# CristmasVillage_Driver_1-2.net
KiCad netlist of a schematic drawn in EAGLE
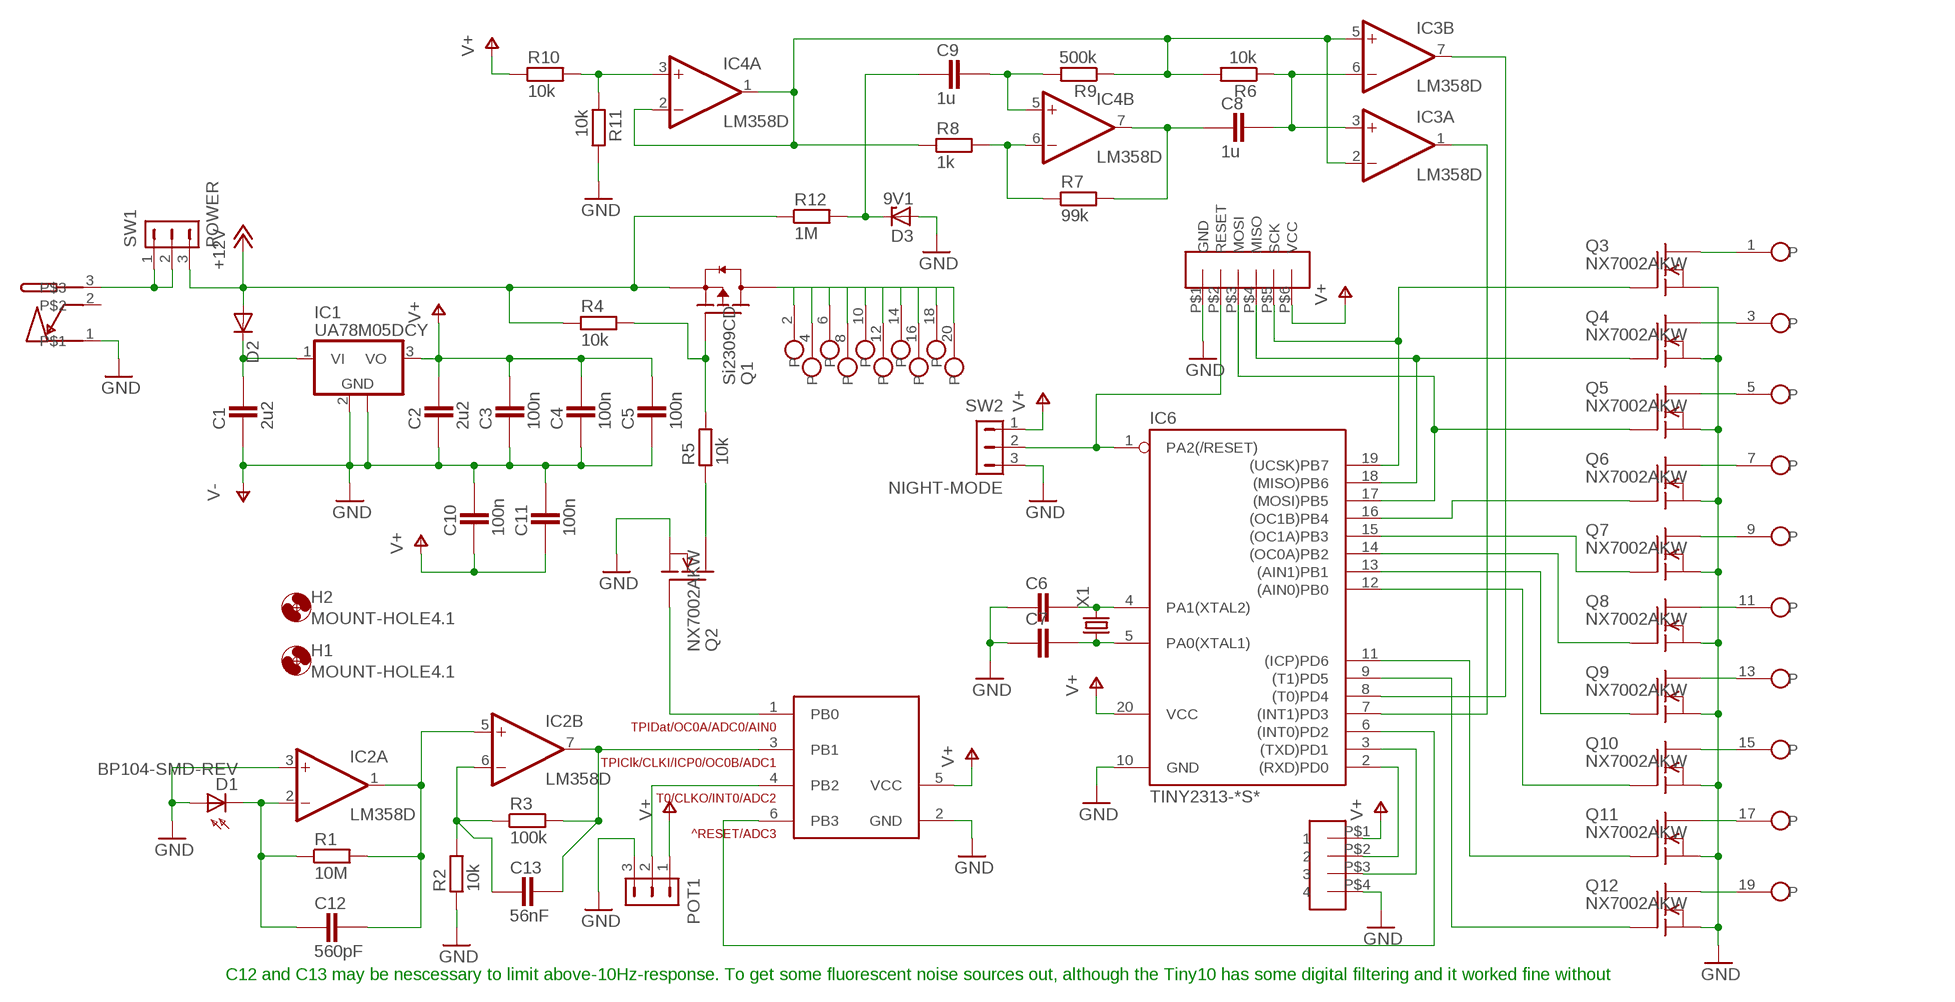
[diagram p0: schematic, sheet 1]

(export (version "E")
  (design (tool "Eeschema 10.0.6"))
  (components
    (comp (ref "C1")
      (value "2u2")
      (footprint "eagle-import:CAPC3215X168N")
      (libsource (lib "eagle-import") (part "CAPACITOR_1206"))
    )
    (comp (ref "C2")
      (value "2u2")
      (footprint "eagle-import:CAPC3215X168N")
      (libsource (lib "eagle-import") (part "CAPACITOR_1206"))
    )
    (comp (ref "C3")
      (value "100n")
      (footprint "eagle-import:CAPC1608X92N")
      (libsource (lib "eagle-import") (part "CAPACITOR_0603"))
    )
    (comp (ref "C4")
      (value "100n")
      (footprint "eagle-import:CAPC1608X92N")
      (libsource (lib "eagle-import") (part "CAPACITOR_0603"))
    )
    (comp (ref "C5")
      (value "100n")
      (footprint "eagle-import:CAPC1608X92N")
      (libsource (lib "eagle-import") (part "CAPACITOR_0603"))
    )
    (comp (ref "C6")
      (value "CAPACITOR_0603")
      (footprint "eagle-import:CAPC1608X92N")
      (libsource (lib "eagle-import") (part "CAPACITOR_0603"))
    )
    (comp (ref "C7")
      (value "CAPACITOR_0603")
      (footprint "eagle-import:CAPC1608X92N")
      (libsource (lib "eagle-import") (part "CAPACITOR_0603"))
    )
    (comp (ref "C8")
      (value "1u")
      (footprint "eagle-import:CAPC3215X168N")
      (libsource (lib "eagle-import") (part "CAPACITOR_1206"))
    )
    (comp (ref "C9")
      (value "1u")
      (footprint "eagle-import:CAPC3215X168N")
      (libsource (lib "eagle-import") (part "CAPACITOR_1206"))
    )
    (comp (ref "C10")
      (value "100n")
      (footprint "eagle-import:CAPC1608X92N")
      (libsource (lib "eagle-import") (part "CAPACITOR_0603"))
    )
    (comp (ref "C11")
      (value "100n")
      (footprint "eagle-import:CAPC1608X92N")
      (libsource (lib "eagle-import") (part "CAPACITOR_0603"))
    )
    (comp (ref "C12")
      (value "560pF")
      (footprint "eagle-import:CAPC1608X92N")
      (libsource (lib "eagle-import") (part "CAPACITOR_0603"))
    )
    (comp (ref "C13")
      (value "56nF")
      (footprint "eagle-import:CAPC1608X92N")
      (libsource (lib "eagle-import") (part "CAPACITOR_0603"))
    )
    (comp (ref "CN1")
      (value "MJ-180SMT")
      (footprint "eagle-import:MJ-180SMT")
      (libsource (lib "eagle-import") (part "MJ-180SMT"))
    )
    (comp (ref "CN2-PROG")
      (value "JST-6PSPI-SIDE-S6B")
      (footprint "eagle-import:6P-H")
      (libsource (lib "eagle-import") (part "JST-6PSPI-SIDE-S6B"))
    )
    (comp (ref "CN3-SERIAL")
      (value "JST-4PSIDE-S4B")
      (footprint "eagle-import:4P-H")
      (libsource (lib "eagle-import") (part "JST-4PSIDE-S4B"))
    )
    (comp (ref "CN5-LEDSTRIPS")
      (value "HDR_2X10_SIDE-MOUNT")
      (footprint "eagle-import:20PIN-10TOP-10BOT")
      (libsource (lib "eagle-import") (part "HDR_2X10_SIDE-MOUNT"))
    )
    (comp (ref "D1")
      (value "BP104-SMD-REV")
      (footprint "eagle-import:BR104SMDREV")
      (libsource (lib "eagle-import") (part "BP104-SMD-REV"))
    )
    (comp (ref "D2")
      (value "DIODE-MINIMELF")
      (footprint "eagle-import:MINIMELF")
      (libsource (lib "eagle-import") (part "DIODE-MINIMELF"))
    )
    (comp (ref "D3")
      (value "9V1")
      (footprint "eagle-import:SOT23")
      (libsource (lib "eagle-import") (part "ZENER-DIODESOT23"))
    )
    (comp (ref "H1")
      (value "MOUNT-HOLE4.1")
      (footprint "eagle-import:4,1")
      (libsource (lib "eagle-import") (part "MOUNT-HOLE4.1"))
    )
    (comp (ref "H2")
      (value "MOUNT-HOLE4.1")
      (footprint "eagle-import:4,1")
      (libsource (lib "eagle-import") (part "MOUNT-HOLE4.1"))
    )
    (comp (ref "IC1")
      (value "UA78M05DCY")
      (footprint "eagle-import:SOT223")
      (libsource (lib "eagle-import") (part "UA78MDCY05"))
    )
    (comp (ref "IC2")
      (value "LM358D")
      (footprint "eagle-import:SO08")
      (libsource (lib "eagle-import") (part "LM358D"))
    )
    (comp (ref "IC3")
      (value "LM358D")
      (footprint "eagle-import:SO08")
      (libsource (lib "eagle-import") (part "LM358D"))
    )
    (comp (ref "IC4")
      (value "LM358D")
      (footprint "eagle-import:SO08")
      (libsource (lib "eagle-import") (part "LM358D"))
    )
    (comp (ref "IC5")
      (value "ATTINY-4/5/9/10")
      (footprint "eagle-import:SOT23-6")
      (libsource (lib "eagle-import") (part "ATTINY-4/5/9/10"))
    )
    (comp (ref "IC6")
      (value "TINY2313-*S*")
      (footprint "eagle-import:SO20L$")
      (libsource (lib "eagle-import") (part "TINY2313-S"))
    )
    (comp (ref "POT1")
      (value "HDR-1X3-MTE-100")
      (footprint "eagle-import:MTE-100-3V")
      (libsource (lib "eagle-import") (part "HDR-1X3-MTE-100"))
    )
    (comp (ref "Q1")
      (value "Si2309CD")
      (footprint "eagle-import:SOT95P280X135-3N")
      (libsource (lib "eagle-import") (part "MOSFET-PCH_SOT-23"))
    )
    (comp (ref "Q2")
      (value "NX7002AKW")
      (footprint "eagle-import:SOT323R")
      (libsource (lib "eagle-import") (part "NX7002AKW"))
    )
    (comp (ref "Q3")
      (value "NX7002AKW")
      (footprint "eagle-import:SOT323R")
      (libsource (lib "eagle-import") (part "NX7002AKW"))
    )
    (comp (ref "Q4")
      (value "NX7002AKW")
      (footprint "eagle-import:SOT323R")
      (libsource (lib "eagle-import") (part "NX7002AKW"))
    )
    (comp (ref "Q5")
      (value "NX7002AKW")
      (footprint "eagle-import:SOT323R")
      (libsource (lib "eagle-import") (part "NX7002AKW"))
    )
    (comp (ref "Q6")
      (value "NX7002AKW")
      (footprint "eagle-import:SOT323R")
      (libsource (lib "eagle-import") (part "NX7002AKW"))
    )
    (comp (ref "Q7")
      (value "NX7002AKW")
      (footprint "eagle-import:SOT323R")
      (libsource (lib "eagle-import") (part "NX7002AKW"))
    )
    (comp (ref "Q8")
      (value "NX7002AKW")
      (footprint "eagle-import:SOT323R")
      (libsource (lib "eagle-import") (part "NX7002AKW"))
    )
    (comp (ref "Q9")
      (value "NX7002AKW")
      (footprint "eagle-import:SOT323R")
      (libsource (lib "eagle-import") (part "NX7002AKW"))
    )
    (comp (ref "Q10")
      (value "NX7002AKW")
      (footprint "eagle-import:SOT323R")
      (libsource (lib "eagle-import") (part "NX7002AKW"))
    )
    (comp (ref "Q11")
      (value "NX7002AKW")
      (footprint "eagle-import:SOT323R")
      (libsource (lib "eagle-import") (part "NX7002AKW"))
    )
    (comp (ref "Q12")
      (value "NX7002AKW")
      (footprint "eagle-import:SOT323R")
      (libsource (lib "eagle-import") (part "NX7002AKW"))
    )
    (comp (ref "R1")
      (value "10M")
      (footprint "eagle-import:RESC1608X55N")
      (libsource (lib "eagle-import") (part "RESISTOR_0603"))
    )
    (comp (ref "R2")
      (value "10k")
      (footprint "eagle-import:RESC1608X55N")
      (libsource (lib "eagle-import") (part "RESISTOR_0603"))
    )
    (comp (ref "R3")
      (value "100k")
      (footprint "eagle-import:RESC1608X55N")
      (libsource (lib "eagle-import") (part "RESISTOR_0603"))
    )
    (comp (ref "R4")
      (value "10k")
      (footprint "eagle-import:RESC1608X55N")
      (libsource (lib "eagle-import") (part "RESISTOR_0603"))
    )
    (comp (ref "R5")
      (value "10k")
      (footprint "eagle-import:RESC1608X55N")
      (libsource (lib "eagle-import") (part "RESISTOR_0603"))
    )
    (comp (ref "R6")
      (value "10k")
      (footprint "eagle-import:RESC1608X55N")
      (libsource (lib "eagle-import") (part "RESISTOR_0603"))
    )
    (comp (ref "R7")
      (value "99k")
      (footprint "eagle-import:RESC1608X55N")
      (libsource (lib "eagle-import") (part "RESISTOR_0603"))
    )
    (comp (ref "R8")
      (value "1k")
      (footprint "eagle-import:RESC1608X55N")
      (libsource (lib "eagle-import") (part "RESISTOR_0603"))
    )
    (comp (ref "R9")
      (value "500k")
      (footprint "eagle-import:RESC1608X55N")
      (libsource (lib "eagle-import") (part "RESISTOR_0603"))
    )
    (comp (ref "R10")
      (value "10k")
      (footprint "eagle-import:RESC1608X55N")
      (libsource (lib "eagle-import") (part "RESISTOR_0603"))
    )
    (comp (ref "R11")
      (value "10k")
      (footprint "eagle-import:RESC1608X55N")
      (libsource (lib "eagle-import") (part "RESISTOR_0603"))
    )
    (comp (ref "R12")
      (value "1M")
      (footprint "eagle-import:RESC1608X55N")
      (libsource (lib "eagle-import") (part "RESISTOR_0603"))
    )
    (comp (ref "SW1")
      (value "POWER")
      (footprint "eagle-import:MTE-100-3V")
      (libsource (lib "eagle-import") (part "HDR-1X3-MTE-100"))
    )
    (comp (ref "SW2")
      (value "NIGHT-MODE")
      (footprint "eagle-import:MTE-100-3V")
      (libsource (lib "eagle-import") (part "HDR-1X3-MTE-100"))
    )
    (comp (ref "X1")
      (value "CRYSTALSM49")
      (footprint "eagle-import:SM49")
      (libsource (lib "eagle-import") (part "CRYSTALSM49"))
    )
  )
  (nets
    (net (code "1") (name "+12V") (class "Default")
      (node (ref "D2") (pin "A") (pinfunction "A_A") (pintype "passive"))
      (node (ref "Q1") (pin "2") (pinfunction "S_2") (pintype "passive"))
      (node (ref "R12") (pin "1") (pinfunction "1_1") (pintype "passive"))
      (node (ref "R4") (pin "1") (pinfunction "1_1") (pintype "passive"))
      (node (ref "SW1") (pin "3") (pinfunction "3_3") (pintype "passive"))
    )
    (net (code "2") (name "GND") (class "Default")
      (node (ref "C1") (pin "1") (pinfunction "1_1") (pintype "passive"))
      (node (ref "C10") (pin "2") (pinfunction "2_2") (pintype "passive"))
      (node (ref "C11") (pin "2") (pinfunction "2_2") (pintype "passive"))
      (node (ref "C2") (pin "1") (pinfunction "1_1") (pintype "passive"))
      (node (ref "C3") (pin "1") (pinfunction "1_1") (pintype "passive"))
      (node (ref "C4") (pin "1") (pinfunction "1_1") (pintype "passive"))
      (node (ref "C5") (pin "1") (pinfunction "1_1") (pintype "passive"))
      (node (ref "C6") (pin "1") (pinfunction "1_1") (pintype "passive"))
      (node (ref "C7") (pin "1") (pinfunction "1_1") (pintype "passive"))
      (node (ref "CN1") (pin "1") (pinfunction "P$1_1") (pintype "bidirectional"))
      (node (ref "CN2-PROG") (pin "P$1") (pinfunction "GND_P$1") (pintype "bidirectional"))
      (node (ref "CN3-SERIAL") (pin "P$4") (pinfunction "4_P$4") (pintype "bidirectional"))
      (node (ref "D1") (pin "1") (pinfunction "A_1") (pintype "passive"))
      (node (ref "D3") (pin "1") (pinfunction "A_1") (pintype "passive"))
      (node (ref "IC1") (pin "2") (pinfunction "GND_2") (pintype "passive"))
      (node (ref "IC1") (pin "4") (pinfunction "GND_4") (pintype "passive"))
      (node (ref "IC2") (pin "3") (pinfunction "+IN_3") (pintype "input"))
      (node (ref "IC5") (pin "2") (pinfunction "GND_2") (pintype "bidirectional"))
      (node (ref "IC6") (pin "10") (pinfunction "GND_10") (pintype "power_in"))
      (node (ref "POT1") (pin "3") (pinfunction "3_3") (pintype "passive"))
      (node (ref "Q10") (pin "2") (pinfunction "S_2") (pintype "passive"))
      (node (ref "Q11") (pin "2") (pinfunction "S_2") (pintype "passive"))
      (node (ref "Q12") (pin "2") (pinfunction "S_2") (pintype "passive"))
      (node (ref "Q2") (pin "2") (pinfunction "S_2") (pintype "passive"))
      (node (ref "Q3") (pin "2") (pinfunction "S_2") (pintype "passive"))
      (node (ref "Q4") (pin "2") (pinfunction "S_2") (pintype "passive"))
      (node (ref "Q5") (pin "2") (pinfunction "S_2") (pintype "passive"))
      (node (ref "Q6") (pin "2") (pinfunction "S_2") (pintype "passive"))
      (node (ref "Q7") (pin "2") (pinfunction "S_2") (pintype "passive"))
      (node (ref "Q8") (pin "2") (pinfunction "S_2") (pintype "passive"))
      (node (ref "Q9") (pin "2") (pinfunction "S_2") (pintype "passive"))
      (node (ref "R11") (pin "2") (pinfunction "2_2") (pintype "passive"))
      (node (ref "R2") (pin "1") (pinfunction "1_1") (pintype "passive"))
      (node (ref "SW2") (pin "3") (pinfunction "3_3") (pintype "passive"))
    )
    (net (code "3") (name "Net-(CN1-P$3)") (class "Default")
      (node (ref "CN1") (pin "3") (pinfunction "P$3_3") (pintype "bidirectional"))
      (node (ref "SW1") (pin "1") (pinfunction "1_1") (pintype "passive"))
      (node (ref "SW1") (pin "2") (pinfunction "2_2") (pintype "passive"))
    )
    (net (code "4") (name "Net-(CN2-PROG-MISO)") (class "Default")
      (node (ref "CN2-PROG") (pin "P$4") (pinfunction "MISO_P$4") (pintype "bidirectional"))
      (node (ref "IC6") (pin "18") (pinfunction "(MISO)PB6_18") (pintype "bidirectional"))
      (node (ref "Q4") (pin "1") (pinfunction "G_1") (pintype "passive"))
    )
    (net (code "5") (name "Net-(CN2-PROG-MOSI)") (class "Default")
      (node (ref "CN2-PROG") (pin "P$3") (pinfunction "MOSI_P$3") (pintype "bidirectional"))
      (node (ref "IC6") (pin "17") (pinfunction "(MOSI)PB5_17") (pintype "bidirectional"))
      (node (ref "Q5") (pin "1") (pinfunction "G_1") (pintype "passive"))
    )
    (net (code "6") (name "Net-(CN2-PROG-RESET)") (class "Default")
      (node (ref "CN2-PROG") (pin "P$2") (pinfunction "RESET_P$2") (pintype "bidirectional"))
      (node (ref "IC6") (pin "1") (pinfunction "PA2(/RESET)_1") (pintype "input"))
      (node (ref "SW2") (pin "2") (pinfunction "2_2") (pintype "passive"))
    )
    (net (code "7") (name "Net-(CN2-PROG-SCK)") (class "Default")
      (node (ref "CN2-PROG") (pin "P$5") (pinfunction "SCK_P$5") (pintype "bidirectional"))
      (node (ref "IC6") (pin "19") (pinfunction "(UCSK)PB7_19") (pintype "bidirectional"))
      (node (ref "Q3") (pin "1") (pinfunction "G_1") (pintype "passive"))
    )
    (net (code "8") (name "Net-(CN3-SERIAL-2)") (class "Default")
      (node (ref "CN3-SERIAL") (pin "P$2") (pinfunction "2_P$2") (pintype "bidirectional"))
      (node (ref "IC6") (pin "2") (pinfunction "(RXD)PD0_2") (pintype "bidirectional"))
    )
    (net (code "9") (name "Net-(CN3-SERIAL-3)") (class "Default")
      (node (ref "CN3-SERIAL") (pin "P$3") (pinfunction "3_P$3") (pintype "bidirectional"))
      (node (ref "IC6") (pin "3") (pinfunction "(TXD)PD1_3") (pintype "bidirectional"))
    )
    (net (code "10") (name "Net-(CN5-LEDSTRIPSA-P)") (class "Default")
      (node (ref "CN5-LEDSTRIPS") (pin "1") (pinfunction "P_1") (pintype "bidirectional"))
      (node (ref "Q3") (pin "3") (pinfunction "D_3") (pintype "passive"))
    )
    (net (code "11") (name "Net-(CN5-LEDSTRIPSB-P)") (class "Default")
      (node (ref "CN5-LEDSTRIPS") (pin "10") (pinfunction "P_10") (pintype "bidirectional"))
      (node (ref "CN5-LEDSTRIPS") (pin "12") (pinfunction "P_12") (pintype "bidirectional"))
      (node (ref "CN5-LEDSTRIPS") (pin "14") (pinfunction "P_14") (pintype "bidirectional"))
      (node (ref "CN5-LEDSTRIPS") (pin "16") (pinfunction "P_16") (pintype "bidirectional"))
      (node (ref "CN5-LEDSTRIPS") (pin "18") (pinfunction "P_18") (pintype "bidirectional"))
      (node (ref "CN5-LEDSTRIPS") (pin "2") (pinfunction "P_2") (pintype "bidirectional"))
      (node (ref "CN5-LEDSTRIPS") (pin "20") (pinfunction "P_20") (pintype "bidirectional"))
      (node (ref "CN5-LEDSTRIPS") (pin "4") (pinfunction "P_4") (pintype "bidirectional"))
      (node (ref "CN5-LEDSTRIPS") (pin "6") (pinfunction "P_6") (pintype "bidirectional"))
      (node (ref "CN5-LEDSTRIPS") (pin "8") (pinfunction "P_8") (pintype "bidirectional"))
      (node (ref "Q1") (pin "3") (pinfunction "D_3") (pintype "passive"))
    )
    (net (code "12") (name "Net-(CN5-LEDSTRIPSC-P)") (class "Default")
      (node (ref "CN5-LEDSTRIPS") (pin "11") (pinfunction "P_11") (pintype "bidirectional"))
      (node (ref "Q8") (pin "3") (pinfunction "D_3") (pintype "passive"))
    )
    (net (code "13") (name "Net-(CN5-LEDSTRIPSE-P)") (class "Default")
      (node (ref "CN5-LEDSTRIPS") (pin "13") (pinfunction "P_13") (pintype "bidirectional"))
      (node (ref "Q9") (pin "3") (pinfunction "D_3") (pintype "passive"))
    )
    (net (code "14") (name "Net-(CN5-LEDSTRIPSG-P)") (class "Default")
      (node (ref "CN5-LEDSTRIPS") (pin "15") (pinfunction "P_15") (pintype "bidirectional"))
      (node (ref "Q10") (pin "3") (pinfunction "D_3") (pintype "passive"))
    )
    (net (code "15") (name "Net-(CN5-LEDSTRIPSI-P)") (class "Default")
      (node (ref "CN5-LEDSTRIPS") (pin "17") (pinfunction "P_17") (pintype "bidirectional"))
      (node (ref "Q11") (pin "3") (pinfunction "D_3") (pintype "passive"))
    )
    (net (code "16") (name "Net-(CN5-LEDSTRIPSK-P)") (class "Default")
      (node (ref "CN5-LEDSTRIPS") (pin "19") (pinfunction "P_19") (pintype "bidirectional"))
      (node (ref "Q12") (pin "3") (pinfunction "D_3") (pintype "passive"))
    )
    (net (code "17") (name "Net-(CN5-LEDSTRIPSN-P)") (class "Default")
      (node (ref "CN5-LEDSTRIPS") (pin "3") (pinfunction "P_3") (pintype "bidirectional"))
      (node (ref "Q4") (pin "3") (pinfunction "D_3") (pintype "passive"))
    )
    (net (code "18") (name "Net-(CN5-LEDSTRIPSP-P)") (class "Default")
      (node (ref "CN5-LEDSTRIPS") (pin "5") (pinfunction "P_5") (pintype "bidirectional"))
      (node (ref "Q5") (pin "3") (pinfunction "D_3") (pintype "passive"))
    )
    (net (code "19") (name "Net-(CN5-LEDSTRIPSR-P)") (class "Default")
      (node (ref "CN5-LEDSTRIPS") (pin "7") (pinfunction "P_7") (pintype "bidirectional"))
      (node (ref "Q6") (pin "3") (pinfunction "D_3") (pintype "passive"))
    )
    (net (code "20") (name "Net-(CN5-LEDSTRIPST-P)") (class "Default")
      (node (ref "CN5-LEDSTRIPS") (pin "9") (pinfunction "P_9") (pintype "bidirectional"))
      (node (ref "Q7") (pin "3") (pinfunction "D_3") (pintype "passive"))
    )
    (net (code "21") (name "Net-(D1-C)") (class "Default")
      (node (ref "C12") (pin "1") (pinfunction "1_1") (pintype "passive"))
      (node (ref "D1") (pin "2") (pinfunction "C_2") (pintype "passive"))
      (node (ref "IC2") (pin "2") (pinfunction "-IN_2") (pintype "input"))
      (node (ref "R1") (pin "1") (pinfunction "1_1") (pintype "passive"))
    )
    (net (code "22") (name "Net-(D3-C)") (class "Default")
      (node (ref "C9") (pin "1") (pinfunction "1_1") (pintype "passive"))
      (node (ref "D3") (pin "3") (pinfunction "C_3") (pintype "passive"))
      (node (ref "R12") (pin "2") (pinfunction "2_2") (pintype "passive"))
    )
    (net (code "23") (name "Net-(IC1-VI)") (class "Default")
      (node (ref "C1") (pin "2") (pinfunction "2_2") (pintype "passive"))
      (node (ref "D2") (pin "C") (pinfunction "C_C") (pintype "passive"))
      (node (ref "IC1") (pin "1") (pinfunction "VI_1") (pintype "input"))
    )
    (net (code "24") (name "Net-(IC2A-OUT)") (class "Default")
      (node (ref "C12") (pin "2") (pinfunction "2_2") (pintype "passive"))
      (node (ref "IC2") (pin "1") (pinfunction "OUT_1") (pintype "output"))
      (node (ref "IC2") (pin "5") (pinfunction "+IN_5") (pintype "input"))
      (node (ref "R1") (pin "2") (pinfunction "2_2") (pintype "passive"))
    )
    (net (code "25") (name "Net-(IC2B--IN)") (class "Default")
      (node (ref "C13") (pin "1") (pinfunction "1_1") (pintype "passive"))
      (node (ref "IC2") (pin "6") (pinfunction "-IN_6") (pintype "input"))
      (node (ref "R2") (pin "2") (pinfunction "2_2") (pintype "passive"))
      (node (ref "R3") (pin "1") (pinfunction "1_1") (pintype "passive"))
    )
    (net (code "26") (name "Net-(IC2B-OUT)") (class "Default")
      (node (ref "C13") (pin "2") (pinfunction "2_2") (pintype "passive"))
      (node (ref "IC2") (pin "7") (pinfunction "OUT_7") (pintype "output"))
      (node (ref "IC5") (pin "3") (pinfunction "PB1_3") (pintype "bidirectional"))
      (node (ref "R3") (pin "2") (pinfunction "2_2") (pintype "passive"))
    )
    (net (code "27") (name "Net-(IC3A-+IN)") (class "Default")
      (node (ref "C8") (pin "2") (pinfunction "2_2") (pintype "passive"))
      (node (ref "IC3") (pin "3") (pinfunction "+IN_3") (pintype "input"))
      (node (ref "IC3") (pin "6") (pinfunction "-IN_6") (pintype "input"))
      (node (ref "R6") (pin "1") (pinfunction "1_1") (pintype "passive"))
    )
    (net (code "28") (name "Net-(IC3A--IN)") (class "Default")
      (node (ref "IC3") (pin "2") (pinfunction "-IN_2") (pintype "input"))
      (node (ref "IC3") (pin "5") (pinfunction "+IN_5") (pintype "input"))
      (node (ref "IC4") (pin "1") (pinfunction "OUT_1") (pintype "output"))
      (node (ref "IC4") (pin "2") (pinfunction "-IN_2") (pintype "input"))
      (node (ref "R6") (pin "2") (pinfunction "2_2") (pintype "passive"))
      (node (ref "R8") (pin "1") (pinfunction "1_1") (pintype "passive"))
      (node (ref "R9") (pin "1") (pinfunction "1_1") (pintype "passive"))
    )
    (net (code "29") (name "Net-(IC3A-OUT)") (class "Default")
      (node (ref "IC3") (pin "1") (pinfunction "OUT_1") (pintype "output"))
      (node (ref "IC6") (pin "7") (pinfunction "(INT1)PD3_7") (pintype "bidirectional"))
    )
    (net (code "30") (name "Net-(IC3B-OUT)") (class "Default")
      (node (ref "IC3") (pin "7") (pinfunction "OUT_7") (pintype "output"))
      (node (ref "IC6") (pin "8") (pinfunction "(T0)PD4_8") (pintype "bidirectional"))
    )
    (net (code "31") (name "Net-(IC4A-+IN)") (class "Default")
      (node (ref "IC4") (pin "3") (pinfunction "+IN_3") (pintype "input"))
      (node (ref "R10") (pin "2") (pinfunction "2_2") (pintype "passive"))
      (node (ref "R11") (pin "1") (pinfunction "1_1") (pintype "passive"))
    )
    (net (code "32") (name "Net-(IC4B-+IN)") (class "Default")
      (node (ref "C9") (pin "2") (pinfunction "2_2") (pintype "passive"))
      (node (ref "IC4") (pin "5") (pinfunction "+IN_5") (pintype "input"))
      (node (ref "R9") (pin "2") (pinfunction "2_2") (pintype "passive"))
    )
    (net (code "33") (name "Net-(IC4B--IN)") (class "Default")
      (node (ref "IC4") (pin "6") (pinfunction "-IN_6") (pintype "input"))
      (node (ref "R7") (pin "1") (pinfunction "1_1") (pintype "passive"))
      (node (ref "R8") (pin "2") (pinfunction "2_2") (pintype "passive"))
    )
    (net (code "34") (name "Net-(IC4B-OUT)") (class "Default")
      (node (ref "C8") (pin "1") (pinfunction "1_1") (pintype "passive"))
      (node (ref "IC4") (pin "7") (pinfunction "OUT_7") (pintype "output"))
      (node (ref "R7") (pin "2") (pinfunction "2_2") (pintype "passive"))
    )
    (net (code "35") (name "Net-(IC5-PB0)") (class "Default")
      (node (ref "IC5") (pin "1") (pinfunction "PB0_1") (pintype "bidirectional"))
      (node (ref "Q2") (pin "1") (pinfunction "G_1") (pintype "passive"))
    )
    (net (code "36") (name "Net-(IC5-PB2)") (class "Default")
      (node (ref "IC5") (pin "4") (pinfunction "PB2_4") (pintype "bidirectional"))
      (node (ref "POT1") (pin "2") (pinfunction "2_2") (pintype "passive"))
    )
    (net (code "37") (name "Net-(IC5-PB3)") (class "Default")
      (node (ref "IC5") (pin "6") (pinfunction "PB3_6") (pintype "bidirectional"))
      (node (ref "IC6") (pin "6") (pinfunction "(INT0)PD2_6") (pintype "bidirectional"))
    )
    (net (code "38") (name "Net-(IC6-(AIN0)PB0)") (class "Default")
      (node (ref "IC6") (pin "12") (pinfunction "(AIN0)PB0_12") (pintype "bidirectional"))
      (node (ref "Q10") (pin "1") (pinfunction "G_1") (pintype "passive"))
    )
    (net (code "39") (name "Net-(IC6-(AIN1)PB1)") (class "Default")
      (node (ref "IC6") (pin "13") (pinfunction "(AIN1)PB1_13") (pintype "bidirectional"))
      (node (ref "Q9") (pin "1") (pinfunction "G_1") (pintype "passive"))
    )
    (net (code "40") (name "Net-(IC6-(ICP)PD6)") (class "Default")
      (node (ref "IC6") (pin "11") (pinfunction "(ICP)PD6_11") (pintype "bidirectional"))
      (node (ref "Q11") (pin "1") (pinfunction "G_1") (pintype "passive"))
    )
    (net (code "41") (name "Net-(IC6-(OC0A)PB2)") (class "Default")
      (node (ref "IC6") (pin "14") (pinfunction "(OC0A)PB2_14") (pintype "bidirectional"))
      (node (ref "Q8") (pin "1") (pinfunction "G_1") (pintype "passive"))
    )
    (net (code "42") (name "Net-(IC6-(OC1A)PB3)") (class "Default")
      (node (ref "IC6") (pin "15") (pinfunction "(OC1A)PB3_15") (pintype "bidirectional"))
      (node (ref "Q7") (pin "1") (pinfunction "G_1") (pintype "passive"))
    )
    (net (code "43") (name "Net-(IC6-(OC1B)PB4)") (class "Default")
      (node (ref "IC6") (pin "16") (pinfunction "(OC1B)PB4_16") (pintype "bidirectional"))
      (node (ref "Q6") (pin "1") (pinfunction "G_1") (pintype "passive"))
    )
    (net (code "44") (name "Net-(IC6-(T1)PD5)") (class "Default")
      (node (ref "IC6") (pin "9") (pinfunction "(T1)PD5_9") (pintype "bidirectional"))
      (node (ref "Q12") (pin "1") (pinfunction "G_1") (pintype "passive"))
    )
    (net (code "45") (name "Net-(IC6-PA0(XTAL1))") (class "Default")
      (node (ref "C7") (pin "2") (pinfunction "2_2") (pintype "passive"))
      (node (ref "IC6") (pin "5") (pinfunction "PA0(XTAL1)_5") (pintype "bidirectional"))
      (node (ref "X1") (pin "1") (pinfunction "1_1") (pintype "passive"))
    )
    (net (code "46") (name "Net-(IC6-PA1(XTAL2))") (class "Default")
      (node (ref "C6") (pin "2") (pinfunction "2_2") (pintype "passive"))
      (node (ref "IC6") (pin "4") (pinfunction "PA1(XTAL2)_4") (pintype "bidirectional"))
      (node (ref "X1") (pin "2") (pinfunction "2_2") (pintype "passive"))
    )
    (net (code "47") (name "Net-(Q1-G)") (class "Default")
      (node (ref "Q1") (pin "1") (pinfunction "G_1") (pintype "passive"))
      (node (ref "R4") (pin "2") (pinfunction "2_2") (pintype "passive"))
      (node (ref "R5") (pin "2") (pinfunction "2_2") (pintype "passive"))
    )
    (net (code "48") (name "Net-(Q2-D)") (class "Default")
      (node (ref "Q2") (pin "3") (pinfunction "D_3") (pintype "passive"))
      (node (ref "R5") (pin "1") (pinfunction "1_1") (pintype "passive"))
    )
    (net (code "49") (name "V+") (class "Default")
      (node (ref "C10") (pin "1") (pinfunction "1_1") (pintype "passive"))
      (node (ref "C11") (pin "1") (pinfunction "1_1") (pintype "passive"))
      (node (ref "C2") (pin "2") (pinfunction "2_2") (pintype "passive"))
      (node (ref "C3") (pin "2") (pinfunction "2_2") (pintype "passive"))
      (node (ref "C4") (pin "2") (pinfunction "2_2") (pintype "passive"))
      (node (ref "C5") (pin "2") (pinfunction "2_2") (pintype "passive"))
      (node (ref "CN2-PROG") (pin "P$6") (pinfunction "VCC_P$6") (pintype "bidirectional"))
      (node (ref "CN3-SERIAL") (pin "P$1") (pinfunction "1_P$1") (pintype "bidirectional"))
      (node (ref "IC1") (pin "3") (pinfunction "VO_3") (pintype "passive"))
      (node (ref "IC5") (pin "5") (pinfunction "VCC_5") (pintype "bidirectional"))
      (node (ref "IC6") (pin "20") (pinfunction "VCC_20") (pintype "power_in"))
      (node (ref "POT1") (pin "1") (pinfunction "1_1") (pintype "passive"))
      (node (ref "R10") (pin "1") (pinfunction "1_1") (pintype "passive"))
      (node (ref "SW2") (pin "1") (pinfunction "1_1") (pintype "passive"))
    )
    (net (code "50") (name "unconnected-(CN1-P$2-Pad2)") (class "Default")
      (node (ref "CN1") (pin "2") (pinfunction "P$2_2") (pintype "bidirectional"))
    )
  )
)
